# MCU.net
KiCad netlist of a schematic drawn in Altium Designer
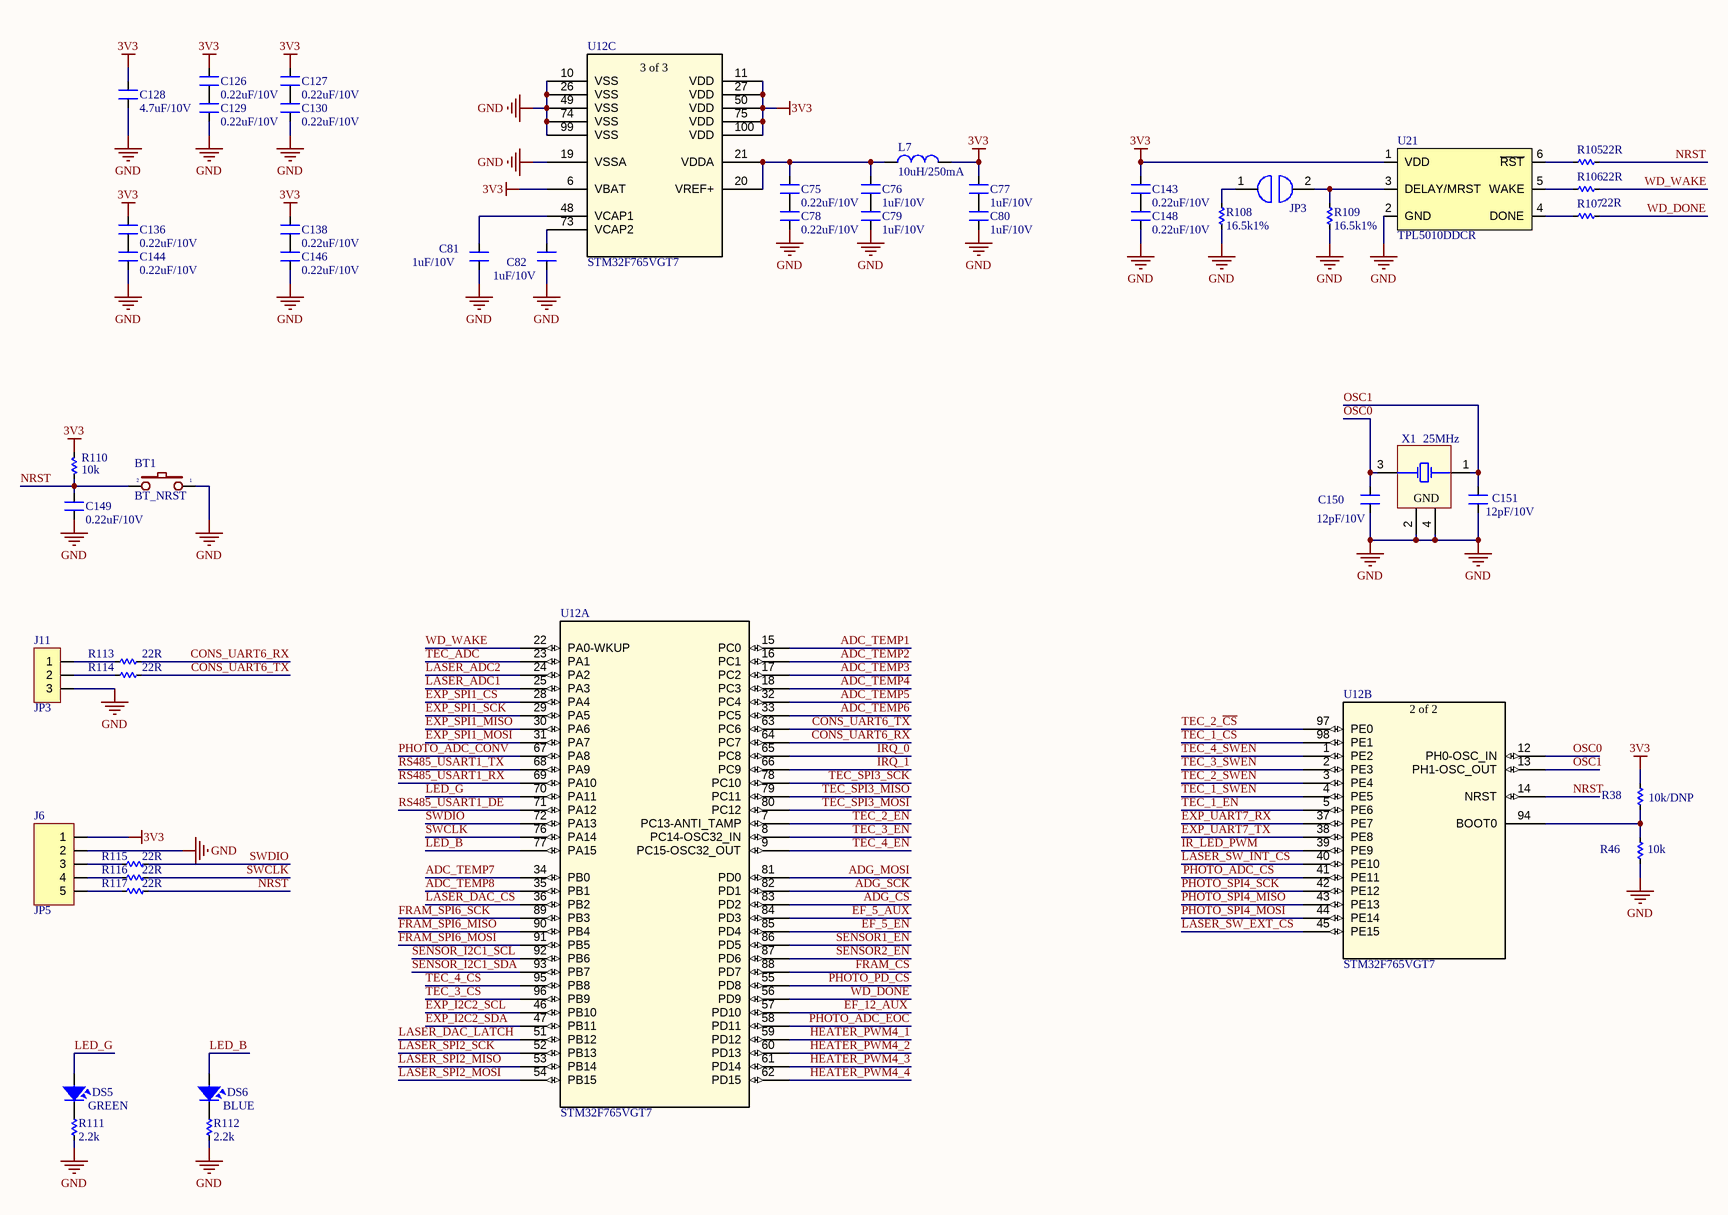
[diagram p0: MCU.SchDoc]

(export (version "E")
  (design (tool "Eeschema 10.0.6"))
  (components
    (comp (ref "BT1")
      (value "BT_NRST")
      (footprint "SW1-SMD")
      (description "Switch button 2 pin")
      (libsource (lib "EXP_HW_V3") (part "SW2"))
    )
    (comp (ref "C75")
      (value "0.22uF/10V")
      (footprint "CAP_C_1608X80")
      (libsource (lib "EXP_HW_V3") (part "Capacitors"))
    )
    (comp (ref "C76")
      (value "1uF/10V")
      (footprint "CAP_C_1608X80")
      (libsource (lib "EXP_HW_V3") (part "Capacitors"))
    )
    (comp (ref "C77")
      (value "1uF/10V")
      (footprint "CAP_C_1608X80")
      (libsource (lib "EXP_HW_V3") (part "Capacitors"))
    )
    (comp (ref "C78")
      (value "0.22uF/10V")
      (footprint "CAP_C_1608X80")
      (libsource (lib "EXP_HW_V3") (part "Capacitors"))
    )
    (comp (ref "C79")
      (value "1uF/10V")
      (footprint "CAP_C_1608X80")
      (libsource (lib "EXP_HW_V3") (part "Capacitors"))
    )
    (comp (ref "C80")
      (value "1uF/10V")
      (footprint "CAP_C_1608X80")
      (libsource (lib "EXP_HW_V3") (part "Capacitors"))
    )
    (comp (ref "C81")
      (value "1uF/10V")
      (footprint "CAP_C_1608X80")
      (libsource (lib "EXP_HW_V3") (part "Capacitors"))
    )
    (comp (ref "C82")
      (value "1uF/10V")
      (footprint "CAP_C_1608X80")
      (libsource (lib "EXP_HW_V3") (part "Capacitors"))
    )
    (comp (ref "C126")
      (value "0.22uF/10V")
      (footprint "CAP_C_1608X80")
      (libsource (lib "EXP_HW_V3") (part "Capacitors"))
    )
    (comp (ref "C127")
      (value "0.22uF/10V")
      (footprint "CAP_C_1608X80")
      (libsource (lib "EXP_HW_V3") (part "Capacitors"))
    )
    (comp (ref "C128")
      (value "4.7uF/10V")
      (footprint "CAP_C_1608X80")
      (libsource (lib "EXP_HW_V3") (part "Capacitors"))
    )
    (comp (ref "C129")
      (value "0.22uF/10V")
      (footprint "CAP_C_1608X80")
      (libsource (lib "EXP_HW_V3") (part "Capacitors"))
    )
    (comp (ref "C130")
      (value "0.22uF/10V")
      (footprint "CAP_C_1608X80")
      (libsource (lib "EXP_HW_V3") (part "Capacitors"))
    )
    (comp (ref "C136")
      (value "0.22uF/10V")
      (footprint "CAP_C_1608X80")
      (libsource (lib "EXP_HW_V3") (part "Capacitors"))
    )
    (comp (ref "C138")
      (value "0.22uF/10V")
      (footprint "CAP_C_1608X80")
      (libsource (lib "EXP_HW_V3") (part "Capacitors"))
    )
    (comp (ref "C143")
      (value "0.22uF/10V")
      (footprint "CAP_C_1608X80")
      (libsource (lib "EXP_HW_V3") (part "Capacitors"))
    )
    (comp (ref "C144")
      (value "0.22uF/10V")
      (footprint "CAP_C_1608X80")
      (libsource (lib "EXP_HW_V3") (part "Capacitors"))
    )
    (comp (ref "C146")
      (value "0.22uF/10V")
      (footprint "CAP_C_1608X80")
      (libsource (lib "EXP_HW_V3") (part "Capacitors"))
    )
    (comp (ref "C148")
      (value "0.22uF/10V")
      (footprint "CAP_C_1608X80")
      (libsource (lib "EXP_HW_V3") (part "Capacitors"))
    )
    (comp (ref "C149")
      (value "0.22uF/10V")
      (footprint "CAP_C_1608X80")
      (libsource (lib "EXP_HW_V3") (part "Capacitors"))
    )
    (comp (ref "C150")
      (value "12pF/10V")
      (footprint "CAP_C_1608X80")
      (libsource (lib "EXP_HW_V3") (part "Capacitors"))
    )
    (comp (ref "C151")
      (value "12pF/10V")
      (footprint "CAP_C_1608X80")
      (libsource (lib "EXP_HW_V3") (part "Capacitors"))
    )
    (comp (ref "DS5")
      (value "GREEN")
      (footprint "LED-0603-BLUE")
      (libsource (lib "EXP_HW_V3") (part "LED SMD"))
    )
    (comp (ref "DS6")
      (value "BLUE")
      (footprint "LED-0603-BLUE")
      (libsource (lib "EXP_HW_V3") (part "LED SMD"))
    )
    (comp (ref "J6")
      (value "JP5")
      (footprint "JP5-D1C")
      (description "WR-PHD 2.54 mm Angled Socket Header")
      (fields
        (field (name "MANUFACTURER") "Würth Elektronik eiSos GmbH")
        (field (name "PARTNO") "613005143121")
        (field (name "CREATED BY") "Karrer Zheng")
      )
      (libsource (lib "EXP_HW_V3") (part "JP5"))
    )
    (comp (ref "J11")
      (value "JP3")
      (footprint "JP3-D1C")
      (description "WR-PHD 2.54 mm Angled Socket Header")
      (fields
        (field (name "MANUFACTURER") "Würth Elektronik eiSos GmbH")
        (field (name "PARTNO") "613003143121")
        (field (name "CREATED BY") "Karrer Zheng")
      )
      (libsource (lib "EXP_HW_V3") (part "JP3"))
    )
    (comp (ref "JP3") (value "jumper2") (footprint "JUMPER2") (libsource (lib "EXP_HW_V3") (part "JUMPER")))
    (comp (ref "L7")
      (value "10uH/250mA")
      (footprint "L-SMD-0603")
      (fields
        (field (name "PARTNO") "78477010")
        (field (name "MANUFACTURER") "Wurth Elektronik")
        (field (name "CREATED BY") "Baojun Chen")
      )
      (libsource (lib "EXP_HW_V3") (part "L-SMD-1"))
    )
    (comp (ref "R38")
      (value "10k/DNP")
      (footprint "RES_C_1608X60")
      (description "SMD")
      (fields
        (field (name "MANUFACTURER") "Generic Components")
        (field (name "PUBLISHER") "Altium Hobart Technology Centre")
      )
      (libsource (lib "EXP_HW_V3") (part "Res SMD"))
    )
    (comp (ref "R46")
      (value "10k")
      (footprint "RES_C_1608X60")
      (description "SMD")
      (fields
        (field (name "MANUFACTURER") "Generic Components")
        (field (name "PUBLISHER") "Altium Hobart Technology Centre")
      )
      (libsource (lib "EXP_HW_V3") (part "Res SMD"))
    )
    (comp (ref "R105")
      (value "22R")
      (footprint "RES_C_1608X60")
      (description "SMD")
      (fields
        (field (name "MANUFACTURER") "Generic Components")
        (field (name "PUBLISHER") "Altium Hobart Technology Centre")
      )
      (libsource (lib "EXP_HW_V3") (part "Res SMD"))
    )
    (comp (ref "R106")
      (value "22R")
      (footprint "RES_C_1608X60")
      (description "SMD")
      (fields
        (field (name "MANUFACTURER") "Generic Components")
        (field (name "PUBLISHER") "Altium Hobart Technology Centre")
      )
      (libsource (lib "EXP_HW_V3") (part "Res SMD"))
    )
    (comp (ref "R107")
      (value "22R")
      (footprint "RES_C_1608X60")
      (description "SMD")
      (fields
        (field (name "MANUFACTURER") "Generic Components")
        (field (name "PUBLISHER") "Altium Hobart Technology Centre")
      )
      (libsource (lib "EXP_HW_V3") (part "Res SMD"))
    )
    (comp (ref "R108")
      (value "16.5k1%")
      (footprint "RES_C_1608X60")
      (description "SMD")
      (fields
        (field (name "MANUFACTURER") "Generic Components")
        (field (name "PUBLISHER") "Altium Hobart Technology Centre")
      )
      (libsource (lib "EXP_HW_V3") (part "Res SMD"))
    )
    (comp (ref "R109")
      (value "16.5k1%")
      (footprint "RES_C_1608X60")
      (description "SMD")
      (fields
        (field (name "MANUFACTURER") "Generic Components")
        (field (name "PUBLISHER") "Altium Hobart Technology Centre")
      )
      (libsource (lib "EXP_HW_V3") (part "Res SMD"))
    )
    (comp (ref "R110")
      (value "10k")
      (footprint "RES_C_1608X60")
      (description "SMD")
      (fields
        (field (name "MANUFACTURER") "Generic Components")
        (field (name "PUBLISHER") "Altium Hobart Technology Centre")
      )
      (libsource (lib "EXP_HW_V3") (part "Res SMD"))
    )
    (comp (ref "R111")
      (value "2.2k")
      (footprint "RES_C_1608X60")
      (description "SMD")
      (fields
        (field (name "MANUFACTURER") "Generic Components")
        (field (name "PUBLISHER") "Altium Hobart Technology Centre")
      )
      (libsource (lib "EXP_HW_V3") (part "Res SMD"))
    )
    (comp (ref "R112")
      (value "2.2k")
      (footprint "RES_C_1608X60")
      (description "SMD")
      (fields
        (field (name "MANUFACTURER") "Generic Components")
        (field (name "PUBLISHER") "Altium Hobart Technology Centre")
      )
      (libsource (lib "EXP_HW_V3") (part "Res SMD"))
    )
    (comp (ref "R113")
      (value "22R")
      (footprint "RES_C_1608X60")
      (description "SMD")
      (fields
        (field (name "MANUFACTURER") "Generic Components")
        (field (name "PUBLISHER") "Altium Hobart Technology Centre")
      )
      (libsource (lib "EXP_HW_V3") (part "Res SMD"))
    )
    (comp (ref "R114")
      (value "22R")
      (footprint "RES_C_1608X60")
      (description "SMD")
      (fields
        (field (name "MANUFACTURER") "Generic Components")
        (field (name "PUBLISHER") "Altium Hobart Technology Centre")
      )
      (libsource (lib "EXP_HW_V3") (part "Res SMD"))
    )
    (comp (ref "R115")
      (value "22R")
      (footprint "RES_C_1608X60")
      (description "SMD")
      (fields
        (field (name "MANUFACTURER") "Generic Components")
        (field (name "PUBLISHER") "Altium Hobart Technology Centre")
      )
      (libsource (lib "EXP_HW_V3") (part "Res SMD"))
    )
    (comp (ref "R116")
      (value "22R")
      (footprint "RES_C_1608X60")
      (description "SMD")
      (fields
        (field (name "MANUFACTURER") "Generic Components")
        (field (name "PUBLISHER") "Altium Hobart Technology Centre")
      )
      (libsource (lib "EXP_HW_V3") (part "Res SMD"))
    )
    (comp (ref "R117")
      (value "22R")
      (footprint "RES_C_1608X60")
      (description "SMD")
      (fields
        (field (name "MANUFACTURER") "Generic Components")
        (field (name "PUBLISHER") "Altium Hobart Technology Centre")
      )
      (libsource (lib "EXP_HW_V3") (part "Res SMD"))
    )
    (comp (ref "U12")
      (value "STM32F765VGT7")
      (footprint "LQFP100_STM")
      (description "No Description Available")
      (libsource (lib "EXP_HW_V3") (part "STM32F765VGT7"))
    )
    (comp (ref "U21")
      (value "TPL5010DDCR")
      (footprint "TPL5010DDCR")
      (description "IC OSC PROG TIMER TSOT23-6")
      (libsource (lib "EXP_HW_V3") (part "TPL5010DDCR"))
    )
    (comp (ref "X1")
      (value "25MHz")
      (footprint "XTAL_ECS-250-12-33Q-JES-TR")
      (description "Crystal, 8 MHz, -30 to 85 degC, 3.2 x 2.5 x 0.9 mm SMD")
      (libsource (lib "Library") (part "XT4"))
    )
  )
  (nets
    (net (code "1") (name "/ADC_TEMP1") (class "Default")
      (node (ref "U12") (pin "15") (pinfunction "PC0_15") (pintype "bidirectional"))
    )
    (net (code "2") (name "/ADC_TEMP2") (class "Default")
      (node (ref "U12") (pin "16") (pinfunction "PC1_16") (pintype "bidirectional"))
    )
    (net (code "3") (name "/ADC_TEMP3") (class "Default")
      (node (ref "U12") (pin "17") (pinfunction "PC2_17") (pintype "bidirectional"))
    )
    (net (code "4") (name "/ADC_TEMP4") (class "Default")
      (node (ref "U12") (pin "18") (pinfunction "PC3_18") (pintype "bidirectional"))
    )
    (net (code "5") (name "/ADC_TEMP5") (class "Default")
      (node (ref "U12") (pin "32") (pinfunction "PC4_32") (pintype "bidirectional"))
    )
    (net (code "6") (name "/ADC_TEMP6") (class "Default")
      (node (ref "U12") (pin "33") (pinfunction "PC5_33") (pintype "bidirectional"))
    )
    (net (code "7") (name "/ADC_TEMP7") (class "Default")
      (node (ref "U12") (pin "34") (pinfunction "PB0_34") (pintype "bidirectional"))
    )
    (net (code "8") (name "/ADC_TEMP8") (class "Default")
      (node (ref "U12") (pin "35") (pinfunction "PB1_35") (pintype "bidirectional"))
    )
    (net (code "9") (name "/ADG_CS") (class "Default")
      (node (ref "U12") (pin "83") (pinfunction "PD2_83") (pintype "bidirectional"))
    )
    (net (code "10") (name "/ADG_MOSI") (class "Default")
      (node (ref "U12") (pin "81") (pinfunction "PD0_81") (pintype "bidirectional"))
    )
    (net (code "11") (name "/ADG_SCK") (class "Default")
      (node (ref "U12") (pin "82") (pinfunction "PD1_82") (pintype "bidirectional"))
    )
    (net (code "12") (name "/CONS_UART6_RX") (class "Default")
      (node (ref "R113") (pin "1") (pinfunction "1_1") (pintype "passive"))
      (node (ref "U12") (pin "64") (pinfunction "PC7_64") (pintype "bidirectional"))
    )
    (net (code "13") (name "/CONS_UART6_TX") (class "Default")
      (node (ref "R114") (pin "1") (pinfunction "1_1") (pintype "passive"))
      (node (ref "U12") (pin "63") (pinfunction "PC6_63") (pintype "bidirectional"))
    )
    (net (code "14") (name "/EF_5_AUX") (class "Default")
      (node (ref "U12") (pin "84") (pinfunction "PD3_84") (pintype "bidirectional"))
    )
    (net (code "15") (name "/EF_5_EN") (class "Default")
      (node (ref "U12") (pin "85") (pinfunction "PD4_85") (pintype "bidirectional"))
    )
    (net (code "16") (name "/EF_12_AUX") (class "Default")
      (node (ref "U12") (pin "57") (pinfunction "PD10_57") (pintype "bidirectional"))
    )
    (net (code "17") (name "/EXP_I2C2_SCL") (class "Default")
      (node (ref "U12") (pin "46") (pinfunction "PB10_46") (pintype "bidirectional"))
    )
    (net (code "18") (name "/EXP_I2C2_SDA") (class "Default")
      (node (ref "U12") (pin "47") (pinfunction "PB11_47") (pintype "bidirectional"))
    )
    (net (code "19") (name "/EXP_SPI1_CS") (class "Default")
      (node (ref "U12") (pin "28") (pinfunction "PA4_28") (pintype "bidirectional"))
    )
    (net (code "20") (name "/EXP_SPI1_MISO") (class "Default")
      (node (ref "U12") (pin "30") (pinfunction "PA6_30") (pintype "bidirectional"))
    )
    (net (code "21") (name "/EXP_SPI1_MOSI") (class "Default")
      (node (ref "U12") (pin "31") (pinfunction "PA7_31") (pintype "bidirectional"))
    )
    (net (code "22") (name "/EXP_SPI1_SCK") (class "Default")
      (node (ref "U12") (pin "29") (pinfunction "PA5_29") (pintype "bidirectional"))
    )
    (net (code "23") (name "/EXP_UART7_RX") (class "Default")
      (node (ref "U12") (pin "37") (pinfunction "PE7_37") (pintype "bidirectional"))
    )
    (net (code "24") (name "/EXP_UART7_TX") (class "Default")
      (node (ref "U12") (pin "38") (pinfunction "PE8_38") (pintype "bidirectional"))
    )
    (net (code "25") (name "/FRAM_CS") (class "Default")
      (node (ref "U12") (pin "88") (pinfunction "PD7_88") (pintype "bidirectional"))
    )
    (net (code "26") (name "/FRAM_SPI6_MISO") (class "Default")
      (node (ref "U12") (pin "90") (pinfunction "PB4_90") (pintype "bidirectional"))
    )
    (net (code "27") (name "/FRAM_SPI6_MOSI") (class "Default")
      (node (ref "U12") (pin "91") (pinfunction "PB5_91") (pintype "bidirectional"))
    )
    (net (code "28") (name "/FRAM_SPI6_SCK") (class "Default")
      (node (ref "U12") (pin "89") (pinfunction "PB3_89") (pintype "bidirectional"))
    )
    (net (code "29") (name "/HEATER_PWM4_1") (class "Default")
      (node (ref "U12") (pin "59") (pinfunction "PD12_59") (pintype "bidirectional"))
    )
    (net (code "30") (name "/HEATER_PWM4_2") (class "Default")
      (node (ref "U12") (pin "60") (pinfunction "PD13_60") (pintype "bidirectional"))
    )
    (net (code "31") (name "/HEATER_PWM4_3") (class "Default")
      (node (ref "U12") (pin "61") (pinfunction "PD14_61") (pintype "bidirectional"))
    )
    (net (code "32") (name "/HEATER_PWM4_4") (class "Default")
      (node (ref "U12") (pin "62") (pinfunction "PD15_62") (pintype "bidirectional"))
    )
    (net (code "33") (name "/IRQ_0") (class "Default")
      (node (ref "U12") (pin "65") (pinfunction "PC8_65") (pintype "bidirectional"))
    )
    (net (code "34") (name "/IRQ_1") (class "Default")
      (node (ref "U12") (pin "66") (pinfunction "PC9_66") (pintype "bidirectional"))
    )
    (net (code "35") (name "/IR_LED_PWM") (class "Default")
      (node (ref "U12") (pin "39") (pinfunction "PE9_39") (pintype "bidirectional"))
    )
    (net (code "36") (name "/LASER_ADC1") (class "Default")
      (node (ref "U12") (pin "25") (pinfunction "PA3_25") (pintype "bidirectional"))
    )
    (net (code "37") (name "/LASER_ADC2") (class "Default")
      (node (ref "U12") (pin "24") (pinfunction "PA2_24") (pintype "bidirectional"))
    )
    (net (code "38") (name "/LASER_DAC_CS") (class "Default")
      (node (ref "U12") (pin "36") (pinfunction "PB2_36") (pintype "bidirectional"))
    )
    (net (code "39") (name "/LASER_DAC_LATCH") (class "Default")
      (node (ref "U12") (pin "51") (pinfunction "PB12_51") (pintype "bidirectional"))
    )
    (net (code "40") (name "/LASER_SPI2_MISO") (class "Default")
      (node (ref "U12") (pin "53") (pinfunction "PB14_53") (pintype "bidirectional"))
    )
    (net (code "41") (name "/LASER_SPI2_MOSI") (class "Default")
      (node (ref "U12") (pin "54") (pinfunction "PB15_54") (pintype "bidirectional"))
    )
    (net (code "42") (name "/LASER_SPI2_SCK") (class "Default")
      (node (ref "U12") (pin "52") (pinfunction "PB13_52") (pintype "bidirectional"))
    )
    (net (code "43") (name "/LASER_SW_EXT_CS") (class "Default")
      (node (ref "U12") (pin "45") (pinfunction "PE15_45") (pintype "bidirectional"))
    )
    (net (code "44") (name "/LASER_SW_INT_CS") (class "Default")
      (node (ref "U12") (pin "40") (pinfunction "PE10_40") (pintype "bidirectional"))
    )
    (net (code "45") (name "/LED_B") (class "Default")
      (node (ref "DS6") (pin "1") (pinfunction "1_1") (pintype "passive"))
      (node (ref "U12") (pin "77") (pinfunction "PA15_77") (pintype "bidirectional"))
    )
    (net (code "46") (name "/LED_G") (class "Default")
      (node (ref "DS5") (pin "1") (pinfunction "1_1") (pintype "passive"))
      (node (ref "U12") (pin "70") (pinfunction "PA11_70") (pintype "bidirectional"))
    )
    (net (code "47") (name "/NRST") (class "Default")
      (node (ref "BT1") (pin "2") (pinfunction "2_2") (pintype "passive"))
      (node (ref "C149") (pin "2") (pinfunction "2_2") (pintype "passive"))
      (node (ref "R105") (pin "2") (pinfunction "2_2") (pintype "passive"))
      (node (ref "R110") (pin "2") (pinfunction "2_2") (pintype "passive"))
      (node (ref "R117") (pin "1") (pinfunction "1_1") (pintype "passive"))
      (node (ref "U12") (pin "14") (pinfunction "NRST_14") (pintype "bidirectional"))
    )
    (net (code "48") (name "/OSC0") (class "Default")
      (node (ref "C150") (pin "1") (pinfunction "1_1") (pintype "passive"))
      (node (ref "U12") (pin "12") (pinfunction "PH0-OSC_IN_12") (pintype "bidirectional"))
      (node (ref "X1") (pin "3") (pinfunction "XTAL_3") (pintype "passive"))
    )
    (net (code "49") (name "/OSC1") (class "Default")
      (node (ref "C151") (pin "2") (pinfunction "2_2") (pintype "passive"))
      (node (ref "U12") (pin "13") (pinfunction "PH1-OSC_OUT_13") (pintype "bidirectional"))
      (node (ref "X1") (pin "1") (pinfunction "XTAL_1") (pintype "passive"))
    )
    (net (code "50") (name "/PHOTO_ADC_CONV") (class "Default")
      (node (ref "U12") (pin "67") (pinfunction "PA8_67") (pintype "bidirectional"))
    )
    (net (code "51") (name "/PHOTO_ADC_CS") (class "Default")
      (node (ref "U12") (pin "41") (pinfunction "PE11_41") (pintype "bidirectional"))
    )
    (net (code "52") (name "/PHOTO_ADC_EOC") (class "Default")
      (node (ref "U12") (pin "58") (pinfunction "PD11_58") (pintype "bidirectional"))
    )
    (net (code "53") (name "/PHOTO_PD_CS") (class "Default")
      (node (ref "U12") (pin "55") (pinfunction "PD8_55") (pintype "bidirectional"))
    )
    (net (code "54") (name "/PHOTO_SPI4_MISO") (class "Default")
      (node (ref "U12") (pin "43") (pinfunction "PE13_43") (pintype "bidirectional"))
    )
    (net (code "55") (name "/PHOTO_SPI4_MOSI") (class "Default")
      (node (ref "U12") (pin "44") (pinfunction "PE14_44") (pintype "bidirectional"))
    )
    (net (code "56") (name "/PHOTO_SPI4_SCK") (class "Default")
      (node (ref "U12") (pin "42") (pinfunction "PE12_42") (pintype "bidirectional"))
    )
    (net (code "57") (name "/RS485_USART1_DE") (class "Default")
      (node (ref "U12") (pin "71") (pinfunction "PA12_71") (pintype "bidirectional"))
    )
    (net (code "58") (name "/RS485_USART1_RX") (class "Default")
      (node (ref "U12") (pin "69") (pinfunction "PA10_69") (pintype "bidirectional"))
    )
    (net (code "59") (name "/RS485_USART1_TX") (class "Default")
      (node (ref "U12") (pin "68") (pinfunction "PA9_68") (pintype "bidirectional"))
    )
    (net (code "60") (name "/SENSOR1_EN") (class "Default")
      (node (ref "U12") (pin "86") (pinfunction "PD5_86") (pintype "bidirectional"))
    )
    (net (code "61") (name "/SENSOR2_EN") (class "Default")
      (node (ref "U12") (pin "87") (pinfunction "PD6_87") (pintype "bidirectional"))
    )
    (net (code "62") (name "/SENSOR_I2C1_SCL") (class "Default")
      (node (ref "U12") (pin "92") (pinfunction "PB6_92") (pintype "bidirectional"))
    )
    (net (code "63") (name "/SENSOR_I2C1_SDA") (class "Default")
      (node (ref "U12") (pin "93") (pinfunction "PB7_93") (pintype "bidirectional"))
    )
    (net (code "64") (name "/SWCLK") (class "Default")
      (node (ref "R116") (pin "1") (pinfunction "1_1") (pintype "passive"))
      (node (ref "U12") (pin "76") (pinfunction "PA14_76") (pintype "bidirectional"))
    )
    (net (code "65") (name "/SWDIO") (class "Default")
      (node (ref "R115") (pin "1") (pinfunction "1_1") (pintype "passive"))
      (node (ref "U12") (pin "72") (pinfunction "PA13_72") (pintype "bidirectional"))
    )
    (net (code "66") (name "/TEC_1_EN") (class "Default")
      (node (ref "U12") (pin "5") (pinfunction "PE6_5") (pintype "bidirectional"))
    )
    (net (code "67") (name "/TEC_1_SWEN") (class "Default")
      (node (ref "U12") (pin "4") (pinfunction "PE5_4") (pintype "bidirectional"))
    )
    (net (code "68") (name "/TEC_1_~{CS}") (class "Default")
      (node (ref "U12") (pin "98") (pinfunction "PE1_98") (pintype "bidirectional"))
    )
    (net (code "69") (name "/TEC_2_EN") (class "Default")
      (node (ref "U12") (pin "7") (pinfunction "PC13-ANTI_TAMP_7") (pintype "bidirectional"))
    )
    (net (code "70") (name "/TEC_2_SWEN") (class "Default")
      (node (ref "U12") (pin "3") (pinfunction "PE4_3") (pintype "bidirectional"))
    )
    (net (code "71") (name "/TEC_2_~{CS}") (class "Default")
      (node (ref "U12") (pin "97") (pinfunction "PE0_97") (pintype "bidirectional"))
    )
    (net (code "72") (name "/TEC_3_EN") (class "Default")
      (node (ref "U12") (pin "8") (pinfunction "PC14-OSC32_IN_8") (pintype "bidirectional"))
    )
    (net (code "73") (name "/TEC_3_SWEN") (class "Default")
      (node (ref "U12") (pin "2") (pinfunction "PE3_2") (pintype "bidirectional"))
    )
    (net (code "74") (name "/TEC_3_~{CS}") (class "Default")
      (node (ref "U12") (pin "96") (pinfunction "PB9_96") (pintype "bidirectional"))
    )
    (net (code "75") (name "/TEC_4_EN") (class "Default")
      (node (ref "U12") (pin "9") (pinfunction "PC15-OSC32_OUT_9") (pintype "bidirectional"))
    )
    (net (code "76") (name "/TEC_4_SWEN") (class "Default")
      (node (ref "U12") (pin "1") (pinfunction "PE2_1") (pintype "bidirectional"))
    )
    (net (code "77") (name "/TEC_4_~{CS}") (class "Default")
      (node (ref "U12") (pin "95") (pinfunction "PB8_95") (pintype "bidirectional"))
    )
    (net (code "78") (name "/TEC_ADC") (class "Default")
      (node (ref "U12") (pin "23") (pinfunction "PA1_23") (pintype "bidirectional"))
    )
    (net (code "79") (name "/TEC_SPI3_MISO") (class "Default")
      (node (ref "U12") (pin "79") (pinfunction "PC11_79") (pintype "bidirectional"))
    )
    (net (code "80") (name "/TEC_SPI3_MOSI") (class "Default")
      (node (ref "U12") (pin "80") (pinfunction "PC12_80") (pintype "bidirectional"))
    )
    (net (code "81") (name "/TEC_SPI3_SCK") (class "Default")
      (node (ref "U12") (pin "78") (pinfunction "PC10_78") (pintype "bidirectional"))
    )
    (net (code "82") (name "/WD_DONE") (class "Default")
      (node (ref "R107") (pin "2") (pinfunction "2_2") (pintype "passive"))
      (node (ref "U12") (pin "56") (pinfunction "PD9_56") (pintype "bidirectional"))
    )
    (net (code "83") (name "/WD_WAKE") (class "Default")
      (node (ref "R106") (pin "2") (pinfunction "2_2") (pintype "passive"))
      (node (ref "U12") (pin "22") (pinfunction "PA0-WKUP_22") (pintype "bidirectional"))
    )
    (net (code "84") (name "3V3") (class "Default")
      (node (ref "C126") (pin "2") (pinfunction "2_2") (pintype "passive"))
      (node (ref "C127") (pin "2") (pinfunction "2_2") (pintype "passive"))
      (node (ref "C128") (pin "2") (pinfunction "2_2") (pintype "passive"))
      (node (ref "C136") (pin "2") (pinfunction "2_2") (pintype "passive"))
      (node (ref "C138") (pin "2") (pinfunction "2_2") (pintype "passive"))
      (node (ref "C143") (pin "2") (pinfunction "2_2") (pintype "passive"))
      (node (ref "C77") (pin "2") (pinfunction "2_2") (pintype "passive"))
      (node (ref "J6") (pin "1") (pinfunction "1_1") (pintype "passive"))
      (node (ref "L7") (pin "1") (pinfunction "1_1") (pintype "passive"))
      (node (ref "R110") (pin "1") (pinfunction "1_1") (pintype "passive"))
      (node (ref "R38") (pin "1") (pinfunction "1_1") (pintype "passive"))
      (node (ref "U12") (pin "100") (pinfunction "VDD_100") (pintype "power_in"))
      (node (ref "U12") (pin "11") (pinfunction "VDD_11") (pintype "power_in"))
      (node (ref "U12") (pin "27") (pinfunction "VDD_27") (pintype "power_in"))
      (node (ref "U12") (pin "50") (pinfunction "VDD_50") (pintype "power_in"))
      (node (ref "U12") (pin "6") (pinfunction "VBAT_6") (pintype "power_in"))
      (node (ref "U12") (pin "75") (pinfunction "VDD_75") (pintype "power_in"))
      (node (ref "U21") (pin "1") (pinfunction "VDD_1") (pintype "passive"))
    )
    (net (code "85") (name "GND") (class "Default")
      (node (ref "BT1") (pin "1") (pinfunction "1_1") (pintype "passive"))
      (node (ref "C128") (pin "1") (pinfunction "1_1") (pintype "passive"))
      (node (ref "C129") (pin "1") (pinfunction "1_1") (pintype "passive"))
      (node (ref "C130") (pin "1") (pinfunction "1_1") (pintype "passive"))
      (node (ref "C144") (pin "1") (pinfunction "1_1") (pintype "passive"))
      (node (ref "C146") (pin "1") (pinfunction "1_1") (pintype "passive"))
      (node (ref "C148") (pin "1") (pinfunction "1_1") (pintype "passive"))
      (node (ref "C149") (pin "1") (pinfunction "1_1") (pintype "passive"))
      (node (ref "C150") (pin "2") (pinfunction "2_2") (pintype "passive"))
      (node (ref "C151") (pin "1") (pinfunction "1_1") (pintype "passive"))
      (node (ref "C78") (pin "1") (pinfunction "1_1") (pintype "passive"))
      (node (ref "C79") (pin "1") (pinfunction "1_1") (pintype "passive"))
      (node (ref "C80") (pin "1") (pinfunction "1_1") (pintype "passive"))
      (node (ref "C81") (pin "1") (pinfunction "1_1") (pintype "passive"))
      (node (ref "C82") (pin "1") (pinfunction "1_1") (pintype "passive"))
      (node (ref "J11") (pin "3") (pinfunction "3_3") (pintype "passive"))
      (node (ref "J6") (pin "2") (pinfunction "2_2") (pintype "passive"))
      (node (ref "R108") (pin "1") (pinfunction "1_1") (pintype "passive"))
      (node (ref "R109") (pin "1") (pinfunction "1_1") (pintype "passive"))
      (node (ref "R111") (pin "2") (pinfunction "2_2") (pintype "passive"))
      (node (ref "R112") (pin "2") (pinfunction "2_2") (pintype "passive"))
      (node (ref "R46") (pin "2") (pinfunction "2_2") (pintype "passive"))
      (node (ref "U12") (pin "10") (pinfunction "VSS_10") (pintype "power_in"))
      (node (ref "U12") (pin "19") (pinfunction "VSSA_19") (pintype "power_in"))
      (node (ref "U12") (pin "26") (pinfunction "VSS_26") (pintype "power_in"))
      (node (ref "U12") (pin "49") (pinfunction "VSS_49") (pintype "power_in"))
      (node (ref "U12") (pin "74") (pinfunction "VSS_74") (pintype "power_in"))
      (node (ref "U12") (pin "99") (pinfunction "VSS_99") (pintype "power_in"))
      (node (ref "U21") (pin "2") (pinfunction "GND_2") (pintype "passive"))
      (node (ref "X1") (pin "2") (pinfunction "GND_2") (pintype "power_in"))
      (node (ref "X1") (pin "4") (pinfunction "GND_4") (pintype "power_in"))
    )
    (net (code "86") (name "Net-(C75-Pad1)") (class "Default")
      (node (ref "C75") (pin "1") (pinfunction "1_1") (pintype "passive"))
      (node (ref "C78") (pin "2") (pinfunction "2_2") (pintype "passive"))
    )
    (net (code "87") (name "Net-(C76-Pad1)") (class "Default")
      (node (ref "C76") (pin "1") (pinfunction "1_1") (pintype "passive"))
      (node (ref "C79") (pin "2") (pinfunction "2_2") (pintype "passive"))
    )
    (net (code "88") (name "Net-(C77-Pad1)") (class "Default")
      (node (ref "C77") (pin "1") (pinfunction "1_1") (pintype "passive"))
      (node (ref "C80") (pin "2") (pinfunction "2_2") (pintype "passive"))
    )
    (net (code "89") (name "Net-(C126-Pad1)") (class "Default")
      (node (ref "C126") (pin "1") (pinfunction "1_1") (pintype "passive"))
      (node (ref "C129") (pin "2") (pinfunction "2_2") (pintype "passive"))
    )
    (net (code "90") (name "Net-(C127-Pad1)") (class "Default")
      (node (ref "C127") (pin "1") (pinfunction "1_1") (pintype "passive"))
      (node (ref "C130") (pin "2") (pinfunction "2_2") (pintype "passive"))
    )
    (net (code "91") (name "Net-(C136-Pad1)") (class "Default")
      (node (ref "C136") (pin "1") (pinfunction "1_1") (pintype "passive"))
      (node (ref "C144") (pin "2") (pinfunction "2_2") (pintype "passive"))
    )
    (net (code "92") (name "Net-(C138-Pad1)") (class "Default")
      (node (ref "C138") (pin "1") (pinfunction "1_1") (pintype "passive"))
      (node (ref "C146") (pin "2") (pinfunction "2_2") (pintype "passive"))
    )
    (net (code "93") (name "Net-(C143-Pad1)") (class "Default")
      (node (ref "C143") (pin "1") (pinfunction "1_1") (pintype "passive"))
      (node (ref "C148") (pin "2") (pinfunction "2_2") (pintype "passive"))
    )
    (net (code "94") (name "Net-(DS5-Pad2)") (class "Default")
      (node (ref "DS5") (pin "2") (pinfunction "2_2") (pintype "passive"))
      (node (ref "R111") (pin "1") (pinfunction "1_1") (pintype "passive"))
    )
    (net (code "95") (name "Net-(DS6-Pad2)") (class "Default")
      (node (ref "DS6") (pin "2") (pinfunction "2_2") (pintype "passive"))
      (node (ref "R112") (pin "1") (pinfunction "1_1") (pintype "passive"))
    )
    (net (code "96") (name "Net-(J6-Pad3)") (class "Default")
      (node (ref "J6") (pin "3") (pinfunction "3_3") (pintype "passive"))
      (node (ref "R115") (pin "2") (pinfunction "2_2") (pintype "passive"))
    )
    (net (code "97") (name "Net-(J6-Pad4)") (class "Default")
      (node (ref "J6") (pin "4") (pinfunction "4_4") (pintype "passive"))
      (node (ref "R116") (pin "2") (pinfunction "2_2") (pintype "passive"))
    )
    (net (code "98") (name "Net-(J6-Pad5)") (class "Default")
      (node (ref "J6") (pin "5") (pinfunction "5_5") (pintype "passive"))
      (node (ref "R117") (pin "2") (pinfunction "2_2") (pintype "passive"))
    )
    (net (code "99") (name "Net-(J11-Pad1)") (class "Default")
      (node (ref "J11") (pin "1") (pinfunction "1_1") (pintype "passive"))
      (node (ref "R113") (pin "2") (pinfunction "2_2") (pintype "passive"))
    )
    (net (code "100") (name "Net-(J11-Pad2)") (class "Default")
      (node (ref "J11") (pin "2") (pinfunction "2_2") (pintype "passive"))
      (node (ref "R114") (pin "2") (pinfunction "2_2") (pintype "passive"))
    )
    (net (code "101") (name "Net-(JP3-Pad1)") (class "Default")
      (node (ref "JP3") (pin "1") (pinfunction "1_1") (pintype "passive"))
      (node (ref "R108") (pin "2") (pinfunction "2_2") (pintype "passive"))
    )
    (net (code "102") (name "Net-(U12B-BOOT0)") (class "Default")
      (node (ref "R38") (pin "2") (pinfunction "2_2") (pintype "passive"))
      (node (ref "R46") (pin "1") (pinfunction "1_1") (pintype "passive"))
      (node (ref "U12") (pin "94") (pinfunction "BOOT0_94") (pintype "input"))
    )
    (net (code "103") (name "Net-(U12C-VCAP1)") (class "Default")
      (node (ref "C81") (pin "2") (pinfunction "2_2") (pintype "passive"))
      (node (ref "U12") (pin "48") (pinfunction "VCAP1_48") (pintype "power_in"))
    )
    (net (code "104") (name "Net-(U12C-VCAP2)") (class "Default")
      (node (ref "C82") (pin "2") (pinfunction "2_2") (pintype "passive"))
      (node (ref "U12") (pin "73") (pinfunction "VCAP2_73") (pintype "power_in"))
    )
    (net (code "105") (name "Net-(U12C-VDDA)") (class "Default")
      (node (ref "C75") (pin "2") (pinfunction "2_2") (pintype "passive"))
      (node (ref "C76") (pin "2") (pinfunction "2_2") (pintype "passive"))
      (node (ref "L7") (pin "2") (pinfunction "2_2") (pintype "passive"))
      (node (ref "U12") (pin "20") (pinfunction "VREF+_20") (pintype "power_in"))
      (node (ref "U12") (pin "21") (pinfunction "VDDA_21") (pintype "power_in"))
    )
    (net (code "106") (name "Net-(U21-DELAY{slash}MRST)") (class "Default")
      (node (ref "JP3") (pin "2") (pinfunction "2_2") (pintype "passive"))
      (node (ref "R109") (pin "2") (pinfunction "2_2") (pintype "passive"))
      (node (ref "U21") (pin "3") (pinfunction "DELAY/MRST_3") (pintype "passive"))
    )
    (net (code "107") (name "Net-(U21-DONE)") (class "Default")
      (node (ref "R107") (pin "1") (pinfunction "1_1") (pintype "passive"))
      (node (ref "U21") (pin "4") (pinfunction "DONE_4") (pintype "passive"))
    )
    (net (code "108") (name "Net-(U21-WAKE)") (class "Default")
      (node (ref "R106") (pin "1") (pinfunction "1_1") (pintype "passive"))
      (node (ref "U21") (pin "5") (pinfunction "WAKE_5") (pintype "passive"))
    )
    (net (code "109") (name "Net-(U21-~{RST})") (class "Default")
      (node (ref "R105") (pin "1") (pinfunction "1_1") (pintype "passive"))
      (node (ref "U21") (pin "6") (pinfunction "~{RST}_6") (pintype "passive"))
    )
  )
)
